# Seeeduino_co2.net
KiCad netlist of a schematic drawn in EAGLE
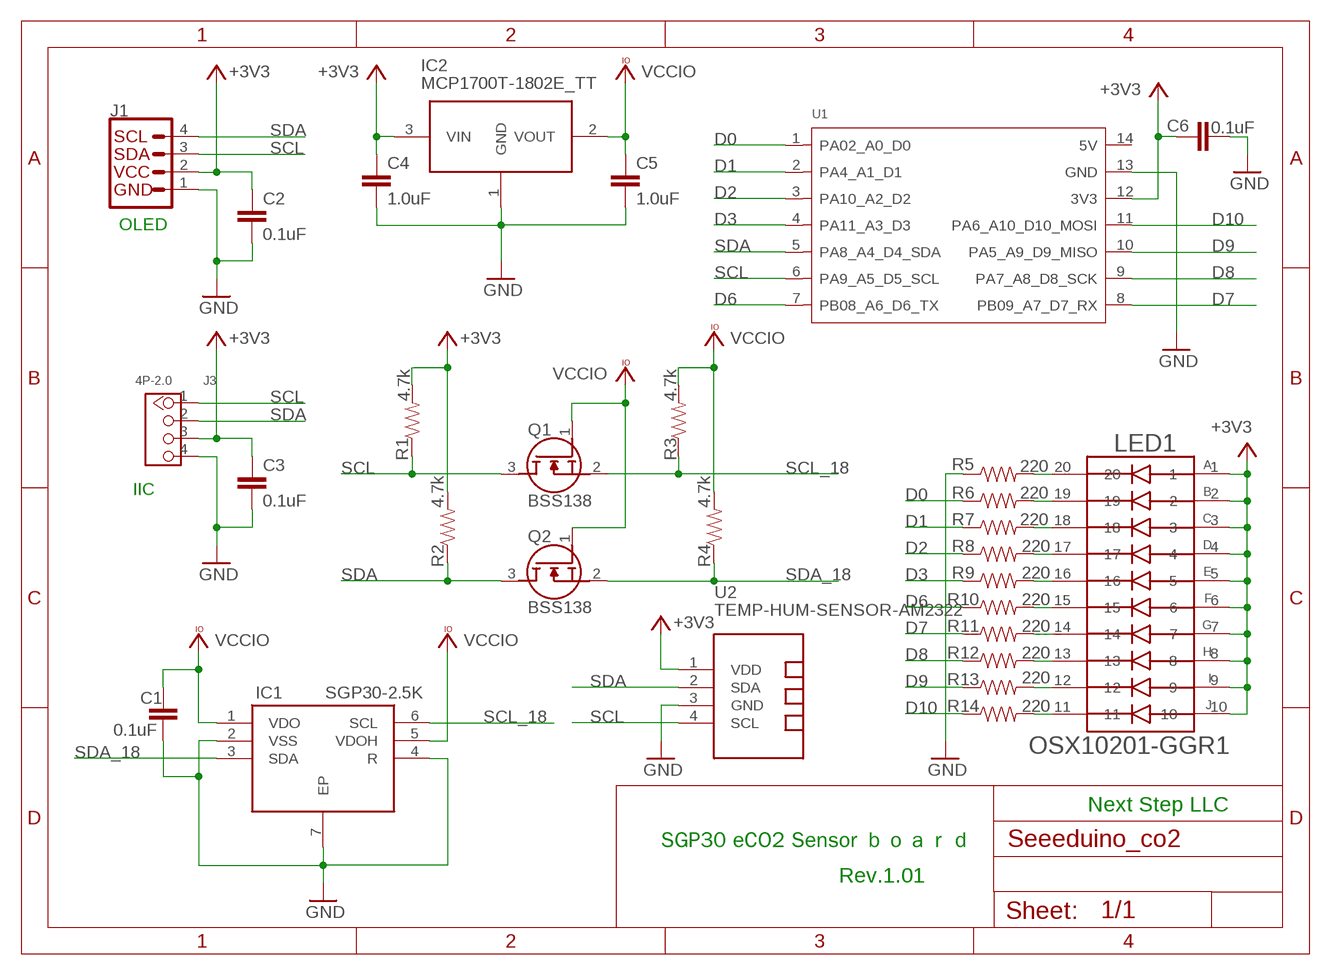
[diagram p0: schematic, sheet 1]

(export (version "E")
  (design (tool "Eeschema 10.0.6"))
  (components
    (comp (ref "C1")
      (value "0.1uF")
      (footprint "eagle-import:0402")
      (libsource (lib "eagle-import") (part "1.0UF-0402-16V-10%"))
    )
    (comp (ref "C2")
      (value "0.1uF")
      (footprint "eagle-import:0402")
      (libsource (lib "eagle-import") (part "1.0UF-0402-16V-10%"))
    )
    (comp (ref "C3")
      (value "0.1uF")
      (footprint "eagle-import:0402")
      (libsource (lib "eagle-import") (part "1.0UF-0402-16V-10%"))
    )
    (comp (ref "C4")
      (value "1.0uF")
      (footprint "eagle-import:0402")
      (libsource (lib "eagle-import") (part "1.0UF-0402-16V-10%"))
    )
    (comp (ref "C5")
      (value "1.0uF")
      (footprint "eagle-import:0402")
      (libsource (lib "eagle-import") (part "1.0UF-0402-16V-10%"))
    )
    (comp (ref "C6")
      (value "0.1uF")
      (footprint "eagle-import:0402")
      (libsource (lib "eagle-import") (part "1.0UF-0402-16V-10%"))
    )
    (comp (ref "IC1")
      (value "SGP30-2.5K")
      (footprint "eagle-import:SON80P245X245X90-7N")
      (fields
        (field (name "MANUFACTURER_PART_NUMBER") "SGP30-2.5k")
        (field (name "MOUSER_PART_NUMBER") "403-SGP30-2.5K")
      )
      (libsource (lib "eagle-import") (part "SGP30-2.5K"))
    )
    (comp (ref "IC2")
      (value "MCP1700T-1802E_TT")
      (footprint "eagle-import:SOT95P237X112-3N")
      (fields
        (field (name "MANUFACTURER_PART_NUMBER") "MCP1700T-1802E/TT")
        (field (name "MOUSER_PART_NUMBER") "579-MCP1700T1802E/TT")
      )
      (libsource (lib "eagle-import") (part "MCP1700T-1802E_TT"))
    )
    (comp (ref "J1")
      (value "I2C_STANDARD")
      (footprint "eagle-import:1X04")
      (libsource (lib "eagle-import") (part "I2C_STANDARD"))
    )
    (comp (ref "J3")
      (value "4P-2.0")
      (footprint "eagle-import:HW4-2.0")
      (libsource (lib "eagle-import") (part "GROVE-CONNECTOR-DIP(4P-2.0)"))
    )
    (comp (ref "LED1")
      (value "OSX10201-GGR1")
      (footprint "eagle-import:DIP760W45P254L2550H790Q20")
      (fields (field (name "MF") "OptoSupply"))
      (libsource (lib "eagle-import") (part "OSX10201-GGR1"))
    )
    (comp (ref "Q1")
      (value "BSS138")
      (footprint "eagle-import:SOT95P240X120-3N")
      (fields (field (name "MOUSER_PART_NUMBER") "512-BSS138"))
      (libsource (lib "eagle-import") (part "BSS138"))
    )
    (comp (ref "Q2")
      (value "BSS138")
      (footprint "eagle-import:SOT95P240X120-3N")
      (fields (field (name "MOUSER_PART_NUMBER") "512-BSS138"))
      (libsource (lib "eagle-import") (part "BSS138"))
    )
    (comp (ref "R1")
      (value "4.7k")
      (footprint "eagle-import:0603")
      (libsource (lib "eagle-import") (part "750OHM-0603-1/10W-1%"))
    )
    (comp (ref "R2")
      (value "4.7k")
      (footprint "eagle-import:0603")
      (libsource (lib "eagle-import") (part "750OHM-0603-1/10W-1%"))
    )
    (comp (ref "R3")
      (value "4.7k")
      (footprint "eagle-import:0603")
      (libsource (lib "eagle-import") (part "750OHM-0603-1/10W-1%"))
    )
    (comp (ref "R4")
      (value "4.7k")
      (footprint "eagle-import:0603")
      (libsource (lib "eagle-import") (part "750OHM-0603-1/10W-1%"))
    )
    (comp (ref "R5")
      (value "220")
      (footprint "eagle-import:0603")
      (libsource (lib "eagle-import") (part "750OHM-0603-1/10W-1%"))
    )
    (comp (ref "R6")
      (value "220")
      (footprint "eagle-import:0603")
      (libsource (lib "eagle-import") (part "750OHM-0603-1/10W-1%"))
    )
    (comp (ref "R7")
      (value "220")
      (footprint "eagle-import:0603")
      (libsource (lib "eagle-import") (part "750OHM-0603-1/10W-1%"))
    )
    (comp (ref "R8")
      (value "220")
      (footprint "eagle-import:0603")
      (libsource (lib "eagle-import") (part "750OHM-0603-1/10W-1%"))
    )
    (comp (ref "R9")
      (value "220")
      (footprint "eagle-import:0603")
      (libsource (lib "eagle-import") (part "750OHM-0603-1/10W-1%"))
    )
    (comp (ref "R10")
      (value "220")
      (footprint "eagle-import:0603")
      (libsource (lib "eagle-import") (part "750OHM-0603-1/10W-1%"))
    )
    (comp (ref "R11")
      (value "220")
      (footprint "eagle-import:0603")
      (libsource (lib "eagle-import") (part "750OHM-0603-1/10W-1%"))
    )
    (comp (ref "R12")
      (value "220")
      (footprint "eagle-import:0603")
      (libsource (lib "eagle-import") (part "750OHM-0603-1/10W-1%"))
    )
    (comp (ref "R13")
      (value "220")
      (footprint "eagle-import:0603")
      (libsource (lib "eagle-import") (part "750OHM-0603-1/10W-1%"))
    )
    (comp (ref "R14")
      (value "220")
      (footprint "eagle-import:0603")
      (libsource (lib "eagle-import") (part "750OHM-0603-1/10W-1%"))
    )
    (comp (ref "U1")
      (value "MOUDLE-SEEEDUINO-XIAO")
      (footprint "eagle-import:MOUDLE14P-2.54-21X17.8MM")
      (libsource (lib "eagle-import") (part "MOUDLE-SEEEDUINO-XIAO"))
    )
    (comp (ref "U2")
      (value "TEMP-HUM-SENSOR-AM2322")
      (footprint "eagle-import:TEMP-HUM-SENSOR-AM2322")
      (libsource (lib "eagle-import") (part "TEMP-HUM-SENSOR-AM2322"))
    )
  )
  (nets
    (net (code "1") (name "+3V3") (class "Default")
      (node (ref "C2") (pin "1") (pinfunction "1_1") (pintype "passive"))
      (node (ref "C3") (pin "1") (pinfunction "1_1") (pintype "passive"))
      (node (ref "C4") (pin "1") (pinfunction "1_1") (pintype "passive"))
      (node (ref "C6") (pin "1") (pinfunction "1_1") (pintype "passive"))
      (node (ref "IC2") (pin "3") (pinfunction "VIN_3") (pintype "bidirectional"))
      (node (ref "J1") (pin "2") (pinfunction "2_2") (pintype "power_in"))
      (node (ref "J3") (pin "3") (pinfunction "3_3") (pintype "bidirectional"))
      (node (ref "LED1") (pin "1") (pinfunction "1_1") (pintype "passive"))
      (node (ref "LED1") (pin "10") (pinfunction "10_10") (pintype "passive"))
      (node (ref "LED1") (pin "2") (pinfunction "2_2") (pintype "passive"))
      (node (ref "LED1") (pin "3") (pinfunction "3_3") (pintype "passive"))
      (node (ref "LED1") (pin "4") (pinfunction "4_4") (pintype "passive"))
      (node (ref "LED1") (pin "5") (pinfunction "5_5") (pintype "passive"))
      (node (ref "LED1") (pin "6") (pinfunction "6_6") (pintype "passive"))
      (node (ref "LED1") (pin "7") (pinfunction "7_7") (pintype "passive"))
      (node (ref "LED1") (pin "8") (pinfunction "8_8") (pintype "passive"))
      (node (ref "LED1") (pin "9") (pinfunction "9_9") (pintype "passive"))
      (node (ref "R1") (pin "2") (pinfunction "2_2") (pintype "passive"))
      (node (ref "R2") (pin "2") (pinfunction "2_2") (pintype "passive"))
      (node (ref "U1") (pin "12") (pinfunction "3V3_12") (pintype "bidirectional"))
      (node (ref "U2") (pin "1") (pinfunction "VDD_1") (pintype "power_in"))
    )
    (net (code "2") (name "/D0") (class "Default")
      (node (ref "R6") (pin "1") (pinfunction "1_1") (pintype "passive"))
      (node (ref "U1") (pin "1") (pinfunction "PA02_A0_D0_1") (pintype "bidirectional"))
    )
    (net (code "3") (name "/D1") (class "Default")
      (node (ref "R7") (pin "1") (pinfunction "1_1") (pintype "passive"))
      (node (ref "U1") (pin "2") (pinfunction "PA4_A1_D1_2") (pintype "bidirectional"))
    )
    (net (code "4") (name "/D2") (class "Default")
      (node (ref "R8") (pin "1") (pinfunction "1_1") (pintype "passive"))
      (node (ref "U1") (pin "3") (pinfunction "PA10_A2_D2_3") (pintype "bidirectional"))
    )
    (net (code "5") (name "/D3") (class "Default")
      (node (ref "R9") (pin "1") (pinfunction "1_1") (pintype "passive"))
      (node (ref "U1") (pin "4") (pinfunction "PA11_A3_D3_4") (pintype "bidirectional"))
    )
    (net (code "6") (name "/D6") (class "Default")
      (node (ref "R10") (pin "1") (pinfunction "1_1") (pintype "passive"))
      (node (ref "U1") (pin "7") (pinfunction "PB08_A6_D6_TX_7") (pintype "bidirectional"))
    )
    (net (code "7") (name "/D7") (class "Default")
      (node (ref "R11") (pin "1") (pinfunction "1_1") (pintype "passive"))
      (node (ref "U1") (pin "8") (pinfunction "PB09_A7_D7_RX_8") (pintype "bidirectional"))
    )
    (net (code "8") (name "/D8") (class "Default")
      (node (ref "R12") (pin "1") (pinfunction "1_1") (pintype "passive"))
      (node (ref "U1") (pin "9") (pinfunction "PA7_A8_D8_SCK_9") (pintype "bidirectional"))
    )
    (net (code "9") (name "/D9") (class "Default")
      (node (ref "R13") (pin "1") (pinfunction "1_1") (pintype "passive"))
      (node (ref "U1") (pin "10") (pinfunction "PA5_A9_D9_MISO_10") (pintype "bidirectional"))
    )
    (net (code "10") (name "/D10") (class "Default")
      (node (ref "R14") (pin "1") (pinfunction "1_1") (pintype "passive"))
      (node (ref "U1") (pin "11") (pinfunction "PA6_A10_D10_MOSI_11") (pintype "bidirectional"))
    )
    (net (code "11") (name "/SCL") (class "Default")
      (node (ref "J1") (pin "3") (pinfunction "3_3") (pintype "passive"))
      (node (ref "J3") (pin "1") (pinfunction "1_1") (pintype "bidirectional"))
      (node (ref "Q1") (pin "3") (pinfunction "D_3") (pintype "bidirectional"))
      (node (ref "R1") (pin "1") (pinfunction "1_1") (pintype "passive"))
      (node (ref "U1") (pin "6") (pinfunction "PA9_A5_D5_SCL_6") (pintype "bidirectional"))
      (node (ref "U2") (pin "4") (pinfunction "SCL_4") (pintype "bidirectional"))
    )
    (net (code "12") (name "/SCL_18") (class "Default")
      (node (ref "IC1") (pin "6") (pinfunction "SCL_6") (pintype "bidirectional"))
      (node (ref "Q1") (pin "2") (pinfunction "S_2") (pintype "bidirectional"))
      (node (ref "R3") (pin "1") (pinfunction "1_1") (pintype "passive"))
    )
    (net (code "13") (name "/SDA") (class "Default")
      (node (ref "J1") (pin "4") (pinfunction "4_4") (pintype "passive"))
      (node (ref "J3") (pin "2") (pinfunction "2_2") (pintype "bidirectional"))
      (node (ref "Q2") (pin "3") (pinfunction "D_3") (pintype "bidirectional"))
      (node (ref "R2") (pin "1") (pinfunction "1_1") (pintype "passive"))
      (node (ref "U1") (pin "5") (pinfunction "PA8_A4_D4_SDA_5") (pintype "bidirectional"))
      (node (ref "U2") (pin "2") (pinfunction "SDA_2") (pintype "bidirectional"))
    )
    (net (code "14") (name "/SDA_18") (class "Default")
      (node (ref "IC1") (pin "3") (pinfunction "SDA_3") (pintype "bidirectional"))
      (node (ref "Q2") (pin "2") (pinfunction "S_2") (pintype "bidirectional"))
      (node (ref "R4") (pin "1") (pinfunction "1_1") (pintype "passive"))
    )
    (net (code "15") (name "GND") (class "Default")
      (node (ref "C1") (pin "2") (pinfunction "2_2") (pintype "passive"))
      (node (ref "C2") (pin "2") (pinfunction "2_2") (pintype "passive"))
      (node (ref "C3") (pin "2") (pinfunction "2_2") (pintype "passive"))
      (node (ref "C4") (pin "2") (pinfunction "2_2") (pintype "passive"))
      (node (ref "C5") (pin "2") (pinfunction "2_2") (pintype "passive"))
      (node (ref "C6") (pin "2") (pinfunction "2_2") (pintype "passive"))
      (node (ref "IC1") (pin "2") (pinfunction "VSS_2") (pintype "power_in"))
      (node (ref "IC1") (pin "4") (pinfunction "R_4") (pintype "power_in"))
      (node (ref "IC1") (pin "7") (pinfunction "EP_7") (pintype "bidirectional"))
      (node (ref "IC2") (pin "1") (pinfunction "GND_1") (pintype "bidirectional"))
      (node (ref "J1") (pin "1") (pinfunction "1_1") (pintype "power_in"))
      (node (ref "J3") (pin "4") (pinfunction "4_4") (pintype "bidirectional"))
      (node (ref "R5") (pin "1") (pinfunction "1_1") (pintype "passive"))
      (node (ref "U1") (pin "13") (pinfunction "GND_13") (pintype "bidirectional"))
      (node (ref "U2") (pin "3") (pinfunction "GND_3") (pintype "power_in"))
    )
    (net (code "16") (name "Net-(LED1-Pad11)") (class "Default")
      (node (ref "LED1") (pin "11") (pinfunction "11_11") (pintype "passive"))
      (node (ref "R14") (pin "2") (pinfunction "2_2") (pintype "passive"))
    )
    (net (code "17") (name "Net-(LED1-Pad12)") (class "Default")
      (node (ref "LED1") (pin "12") (pinfunction "12_12") (pintype "passive"))
      (node (ref "R13") (pin "2") (pinfunction "2_2") (pintype "passive"))
    )
    (net (code "18") (name "Net-(LED1-Pad13)") (class "Default")
      (node (ref "LED1") (pin "13") (pinfunction "13_13") (pintype "passive"))
      (node (ref "R12") (pin "2") (pinfunction "2_2") (pintype "passive"))
    )
    (net (code "19") (name "Net-(LED1-Pad14)") (class "Default")
      (node (ref "LED1") (pin "14") (pinfunction "14_14") (pintype "passive"))
      (node (ref "R11") (pin "2") (pinfunction "2_2") (pintype "passive"))
    )
    (net (code "20") (name "Net-(LED1-Pad15)") (class "Default")
      (node (ref "LED1") (pin "15") (pinfunction "15_15") (pintype "passive"))
      (node (ref "R10") (pin "2") (pinfunction "2_2") (pintype "passive"))
    )
    (net (code "21") (name "Net-(LED1-Pad16)") (class "Default")
      (node (ref "LED1") (pin "16") (pinfunction "16_16") (pintype "passive"))
      (node (ref "R9") (pin "2") (pinfunction "2_2") (pintype "passive"))
    )
    (net (code "22") (name "Net-(LED1-Pad17)") (class "Default")
      (node (ref "LED1") (pin "17") (pinfunction "17_17") (pintype "passive"))
      (node (ref "R8") (pin "2") (pinfunction "2_2") (pintype "passive"))
    )
    (net (code "23") (name "Net-(LED1-Pad18)") (class "Default")
      (node (ref "LED1") (pin "18") (pinfunction "18_18") (pintype "passive"))
      (node (ref "R7") (pin "2") (pinfunction "2_2") (pintype "passive"))
    )
    (net (code "24") (name "Net-(LED1-Pad19)") (class "Default")
      (node (ref "LED1") (pin "19") (pinfunction "19_19") (pintype "passive"))
      (node (ref "R6") (pin "2") (pinfunction "2_2") (pintype "passive"))
    )
    (net (code "25") (name "Net-(LED1-Pad20)") (class "Default")
      (node (ref "LED1") (pin "20") (pinfunction "20_20") (pintype "passive"))
      (node (ref "R5") (pin "2") (pinfunction "2_2") (pintype "passive"))
    )
    (net (code "26") (name "VCCIO") (class "Default")
      (node (ref "C1") (pin "1") (pinfunction "1_1") (pintype "passive"))
      (node (ref "C5") (pin "1") (pinfunction "1_1") (pintype "passive"))
      (node (ref "IC1") (pin "1") (pinfunction "VDO_1") (pintype "power_in"))
      (node (ref "IC1") (pin "5") (pinfunction "VDOH_5") (pintype "power_in"))
      (node (ref "IC2") (pin "2") (pinfunction "VOUT_2") (pintype "bidirectional"))
      (node (ref "Q1") (pin "1") (pinfunction "G_1") (pintype "bidirectional"))
      (node (ref "Q2") (pin "1") (pinfunction "G_1") (pintype "bidirectional"))
      (node (ref "R3") (pin "2") (pinfunction "2_2") (pintype "passive"))
      (node (ref "R4") (pin "2") (pinfunction "2_2") (pintype "passive"))
    )
    (net (code "27") (name "unconnected-(U1-5V-Pad14)") (class "Default")
      (node (ref "U1") (pin "14") (pinfunction "5V_14") (pintype "bidirectional"))
    )
  )
)
